# Lateral_board.net
KiCad netlist of a schematic drawn in Altium Designer
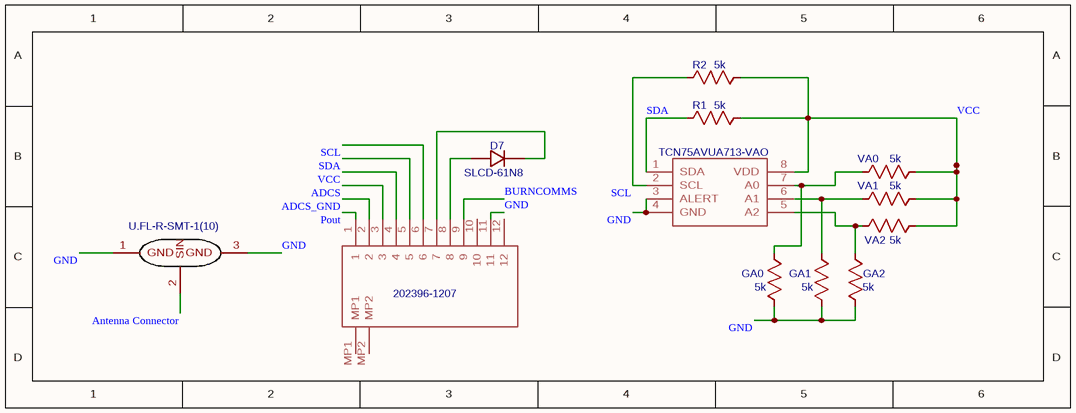
[diagram p0: Lateral_board.schdoc]

(export (version "E")
  (design (tool "Eeschema 10.0.6"))
  (components
    (comp (ref "D7")
      (value "SLCD-61N8")
      (footprint "SOD-123_L2.8-W1.8-LS3.7-RD")
      (fields
        (field (name "BOM_SUPPLIER PART") "C328592")
        (field (name "BOM_MANUFACTURER PART") "1N4007W")
        (field (name "CONTRIBUTOR") "Blothr")
      )
      (libsource (lib "altium-import") (part "root_0_SLCD-61N8_"))
    )
    (comp (ref "GA0")
      (value "5k")
      (footprint "R0805")
      (fields
        (field (name "BOM_SUPPLIER PART") "71-CRCW0805J-5K")
        (field (name "BOM_MANUFACTURER PART") "CRCW08055K00JNTA")
        (field (name "CONTRIBUTOR") "LCEDA_Lib")
      )
      (libsource (lib "altium-import") (part "root_1_5k_"))
    )
    (comp (ref "GA1")
      (value "5k")
      (footprint "R0805")
      (fields
        (field (name "BOM_SUPPLIER PART") "71-CRCW0805J-5K")
        (field (name "BOM_MANUFACTURER PART") "CRCW08055K00JNTA")
        (field (name "CONTRIBUTOR") "LCEDA_Lib")
      )
      (libsource (lib "altium-import") (part "root_1_5k_"))
    )
    (comp (ref "GA2")
      (value "5k")
      (footprint "R0805")
      (fields
        (field (name "BOM_SUPPLIER PART") "71-CRCW0805J-5K")
        (field (name "BOM_MANUFACTURER PART") "CRCW08055K00JNTA")
        (field (name "CONTRIBUTOR") "LCEDA_Lib")
      )
      (libsource (lib "altium-import") (part "root_1_5k_"))
    )
    (comp (ref "IC1")
      (value "TCN75AVUA713-VAO")
      (footprint "SOP65P490X110-8N")
      (libsource (lib "altium-import") (part "root_0_TCN75AVUA713-VAO_"))
    )
    (comp (ref "J1")
      (value "202396-1207")
      (footprint "2023961207")
      (fields (field (name "CONTRIBUTOR") "tomact"))
      (libsource (lib "altium-import") (part "root_1_202396-1207_"))
    )
    (comp (ref "JP1")
      (value "U.FL-R-SMT-1(10)")
      (footprint "ANT-SMD_UFL-R-SMT-1-10")
      (fields (field (name "BOM_SUPPLIER PART") "C88373"))
      (libsource (lib "altium-import") (part "root_0_U.FL-R-SMT-1(10)_"))
    )
    (comp (ref "R1")
      (value "5k")
      (footprint "R0805")
      (fields
        (field (name "BOM_SUPPLIER PART") "71-CRCW0805J-5K")
        (field (name "BOM_MANUFACTURER PART") "CRCW08055K00JNTA")
        (field (name "CONTRIBUTOR") "LCEDA_Lib")
      )
      (libsource (lib "altium-import") (part "root_0_5k_"))
    )
    (comp (ref "R2")
      (value "5k")
      (footprint "R0805")
      (fields
        (field (name "BOM_SUPPLIER PART") "71-CRCW0805J-5K")
        (field (name "BOM_MANUFACTURER PART") "CRCW08055K00JNTA")
        (field (name "CONTRIBUTOR") "LCEDA_Lib")
      )
      (libsource (lib "altium-import") (part "root_0_5k_"))
    )
    (comp (ref "VA0")
      (value "5k")
      (footprint "R0805")
      (fields
        (field (name "BOM_SUPPLIER PART") "71-CRCW0805J-5K")
        (field (name "BOM_MANUFACTURER PART") "CRCW08055K00JNTA")
        (field (name "CONTRIBUTOR") "LCEDA_Lib")
      )
      (libsource (lib "altium-import") (part "root_0_5k_"))
    )
    (comp (ref "VA1")
      (value "5k")
      (footprint "R0805")
      (fields
        (field (name "BOM_SUPPLIER PART") "71-CRCW0805J-5K")
        (field (name "BOM_MANUFACTURER PART") "CRCW08055K00JNTA")
        (field (name "CONTRIBUTOR") "LCEDA_Lib")
      )
      (libsource (lib "altium-import") (part "root_0_5k_"))
    )
    (comp (ref "VA2")
      (value "5k")
      (footprint "R0805")
      (fields
        (field (name "BOM_SUPPLIER PART") "71-CRCW0805J-5K")
        (field (name "BOM_MANUFACTURER PART") "CRCW08055K00JNTA")
        (field (name "CONTRIBUTOR") "LCEDA_Lib")
      )
      (libsource (lib "altium-import") (part "root_0_5k_"))
    )
  )
  (nets
    (net (code "1") (name "/ADCS") (class "Default")
      (node (ref "J1") (pin "3") (pinfunction "3_3") (pintype "passive"))
    )
    (net (code "2") (name "/ADCS_GND") (class "Default")
      (node (ref "J1") (pin "2") (pinfunction "2_2") (pintype "passive"))
    )
    (net (code "3") (name "/Antenna Connector") (class "Default")
      (node (ref "JP1") (pin "2") (pinfunction "SIN_2") (pintype "passive"))
    )
    (net (code "4") (name "/BURNCOMMS") (class "Default")
      (node (ref "J1") (pin "9") (pinfunction "9_9") (pintype "passive"))
    )
    (net (code "5") (name "/GND") (class "Default")
      (node (ref "GA0") (pin "1") (pinfunction "1_1") (pintype "passive"))
      (node (ref "GA1") (pin "1") (pinfunction "1_1") (pintype "passive"))
      (node (ref "GA2") (pin "1") (pinfunction "1_1") (pintype "passive"))
      (node (ref "IC1") (pin "3") (pinfunction "ALERT_3") (pintype "passive"))
      (node (ref "IC1") (pin "4") (pinfunction "GND_4") (pintype "passive"))
      (node (ref "J1") (pin "11") (pinfunction "11_11") (pintype "passive"))
      (node (ref "JP1") (pin "1") (pinfunction "GND_1") (pintype "passive"))
      (node (ref "JP1") (pin "3") (pinfunction "GND_3") (pintype "passive"))
    )
    (net (code "6") (name "/Pout") (class "Default")
      (node (ref "J1") (pin "1") (pinfunction "1_1") (pintype "passive"))
    )
    (net (code "7") (name "/SCL") (class "Default")
      (node (ref "IC1") (pin "2") (pinfunction "SCL_2") (pintype "passive"))
      (node (ref "J1") (pin "6") (pinfunction "6_6") (pintype "passive"))
      (node (ref "R2") (pin "1") (pinfunction "1_1") (pintype "passive"))
    )
    (net (code "8") (name "/SDA") (class "Default")
      (node (ref "IC1") (pin "1") (pinfunction "SDA_1") (pintype "passive"))
      (node (ref "J1") (pin "5") (pinfunction "5_5") (pintype "passive"))
      (node (ref "R1") (pin "1") (pinfunction "1_1") (pintype "passive"))
    )
    (net (code "9") (name "/VCC") (class "Default")
      (node (ref "IC1") (pin "8") (pinfunction "VDD_8") (pintype "passive"))
      (node (ref "J1") (pin "4") (pinfunction "4_4") (pintype "passive"))
      (node (ref "R1") (pin "2") (pinfunction "2_2") (pintype "passive"))
      (node (ref "R2") (pin "2") (pinfunction "2_2") (pintype "passive"))
      (node (ref "VA0") (pin "2") (pinfunction "2_2") (pintype "passive"))
      (node (ref "VA1") (pin "2") (pinfunction "2_2") (pintype "passive"))
      (node (ref "VA2") (pin "2") (pinfunction "2_2") (pintype "passive"))
    )
    (net (code "10") (name "Net-(D7-Pad1)") (class "Default")
      (node (ref "D7") (pin "1") (pinfunction "1_1") (pintype "passive"))
      (node (ref "J1") (pin "7") (pinfunction "7_7") (pintype "passive"))
    )
    (net (code "11") (name "Net-(D7-Pad2)") (class "Default")
      (node (ref "D7") (pin "2") (pinfunction "2_2") (pintype "passive"))
      (node (ref "J1") (pin "8") (pinfunction "8_8") (pintype "passive"))
    )
    (net (code "12") (name "Net-(IC1-A0)") (class "Default")
      (node (ref "GA0") (pin "2") (pinfunction "2_2") (pintype "passive"))
      (node (ref "IC1") (pin "7") (pinfunction "A0_7") (pintype "passive"))
      (node (ref "VA0") (pin "1") (pinfunction "1_1") (pintype "passive"))
    )
    (net (code "13") (name "Net-(IC1-A1)") (class "Default")
      (node (ref "GA1") (pin "2") (pinfunction "2_2") (pintype "passive"))
      (node (ref "IC1") (pin "6") (pinfunction "A1_6") (pintype "passive"))
      (node (ref "VA1") (pin "1") (pinfunction "1_1") (pintype "passive"))
    )
    (net (code "14") (name "Net-(IC1-A2)") (class "Default")
      (node (ref "GA2") (pin "2") (pinfunction "2_2") (pintype "passive"))
      (node (ref "IC1") (pin "5") (pinfunction "A2_5") (pintype "passive"))
      (node (ref "VA2") (pin "1") (pinfunction "1_1") (pintype "passive"))
    )
    (net (code "15") (name "unconnected-(J1-Pad10)") (class "Default")
      (node (ref "J1") (pin "10") (pinfunction "10_10") (pintype "passive"))
    )
    (net (code "16") (name "unconnected-(J1-Pad12)") (class "Default")
      (node (ref "J1") (pin "12") (pinfunction "12_12") (pintype "passive"))
    )
    (net (code "17") (name "unconnected-(J1-PadMP1)") (class "Default")
      (node (ref "J1") (pin "MP1") (pinfunction "MP1_MP1") (pintype "passive"))
    )
    (net (code "18") (name "unconnected-(J1-PadMP2)") (class "Default")
      (node (ref "J1") (pin "MP2") (pinfunction "MP2_MP2") (pintype "passive"))
    )
  )
)
